# Gripper_Finger.net
KiCad netlist of a schematic drawn in EAGLE
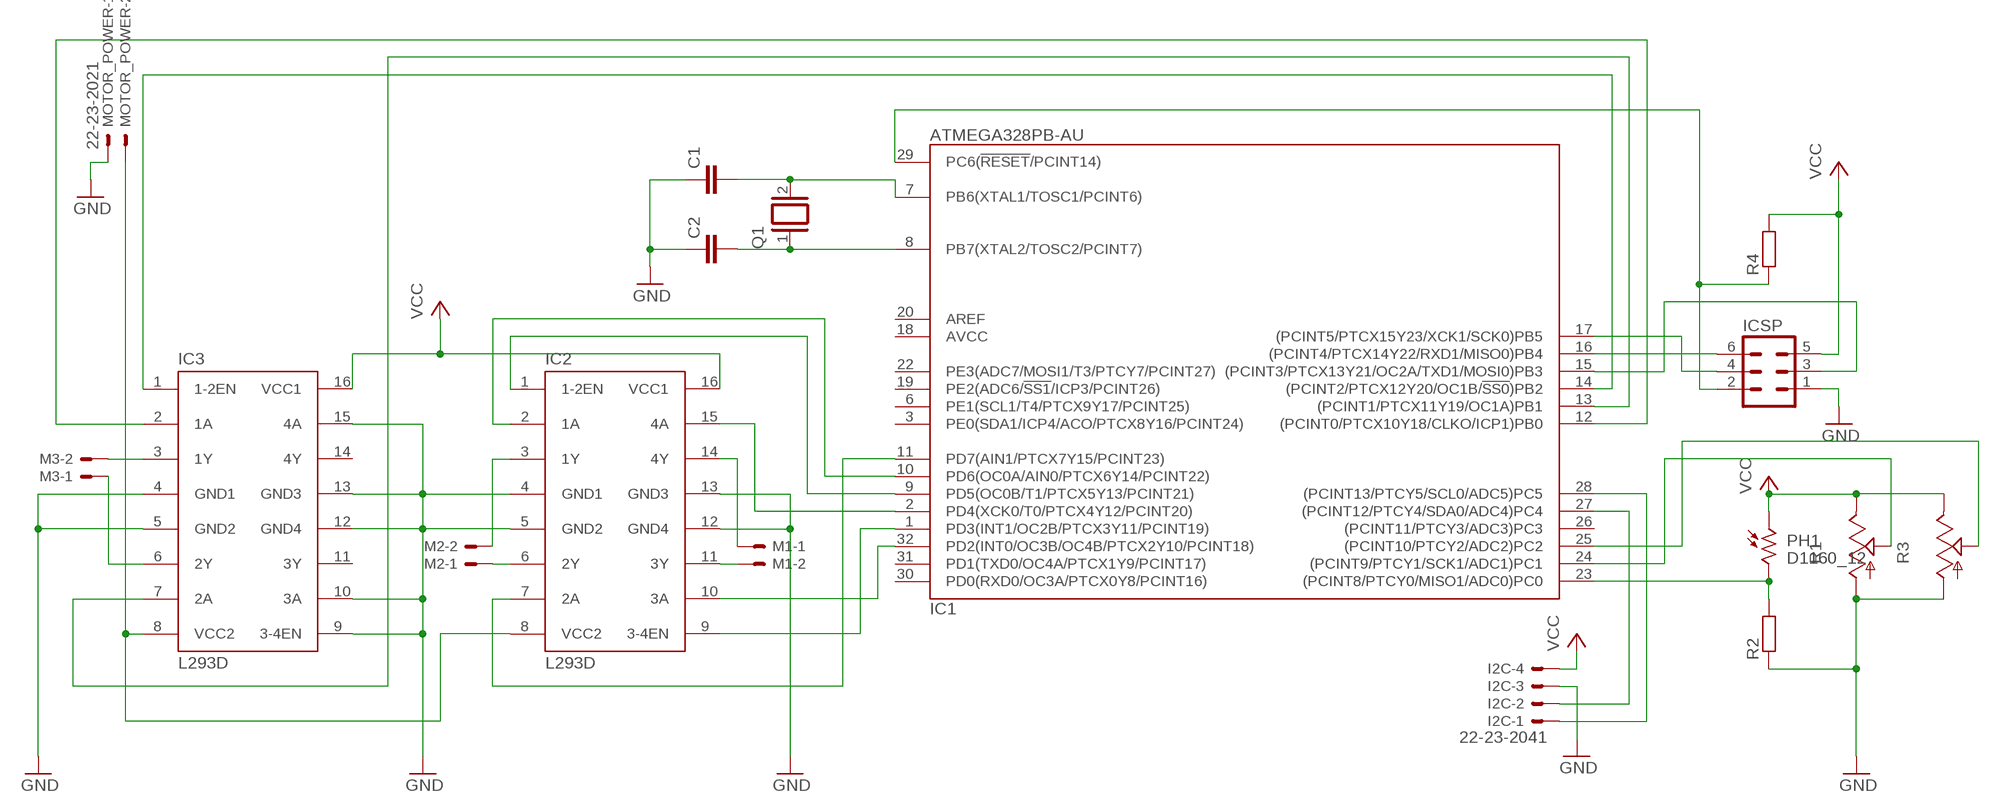
[diagram p0: schematic, sheet 1]

(export (version "E")
  (design (tool "Eeschema 10.0.6"))
  (components
    (comp (ref "C1")
      (value "C2.5/2")
      (footprint "eagle-import:C2.5-2")
      (libsource (lib "eagle-import") (part "C2.5/2"))
    )
    (comp (ref "C2")
      (value "C2.5/2")
      (footprint "eagle-import:C2.5-2")
      (libsource (lib "eagle-import") (part "C2.5/2"))
    )
    (comp (ref "I2C")
      (value "22-23-2041")
      (footprint "eagle-import:22-23-2041")
      (fields (field (name "MF") "MOLEX"))
      (libsource (lib "eagle-import") (part "22-23-2041"))
    )
    (comp (ref "IC1")
      (value "ATMEGA328PB-AU")
      (footprint "eagle-import:QFP32_7X7_0.80")
      (libsource (lib "eagle-import") (part "ATMEGA328PB-AU"))
    )
    (comp (ref "IC2")
      (value "L293D")
      (footprint "eagle-import:DIL16")
      (libsource (lib "eagle-import") (part "L293D"))
    )
    (comp (ref "IC3")
      (value "L293D")
      (footprint "eagle-import:DIL16")
      (libsource (lib "eagle-import") (part "L293D"))
    )
    (comp (ref "ICSP")
      (value "MA03-2")
      (footprint "eagle-import:MA03-2")
      (libsource (lib "eagle-import") (part "MA03-2"))
    )
    (comp (ref "M1")
      (value "22-23-2021")
      (footprint "eagle-import:22-23-2021")
      (fields (field (name "MF") "MOLEX"))
      (libsource (lib "eagle-import") (part "22-23-2021"))
    )
    (comp (ref "M2")
      (value "22-23-2021")
      (footprint "eagle-import:22-23-2021")
      (fields (field (name "MF") "MOLEX"))
      (libsource (lib "eagle-import") (part "22-23-2021"))
    )
    (comp (ref "M3")
      (value "22-23-2021")
      (footprint "eagle-import:22-23-2021")
      (fields (field (name "MF") "MOLEX"))
      (libsource (lib "eagle-import") (part "22-23-2021"))
    )
    (comp (ref "MOTOR_POWER")
      (value "22-23-2021")
      (footprint "eagle-import:22-23-2021")
      (fields (field (name "MF") "MOLEX"))
      (libsource (lib "eagle-import") (part "22-23-2021"))
    )
    (comp (ref "PH1")
      (value "D1160_12")
      (footprint "eagle-import:D11XX")
      (libsource (lib "eagle-import") (part "D1160_12"))
    )
    (comp (ref "Q1")
      (value "XTAL/S")
      (footprint "eagle-import:QS")
      (libsource (lib "eagle-import") (part "XTAL/S"))
    )
    (comp (ref "R1")
      (value "TRIM_US-B64Y")
      (footprint "eagle-import:B64Y")
      (libsource (lib "eagle-import") (part "TRIM_US-B64Y"))
    )
    (comp (ref "R2")
      (value "R-EU_0204/5")
      (footprint "eagle-import:0204_5")
      (libsource (lib "eagle-import") (part "R-EU_0204/5"))
    )
    (comp (ref "R3")
      (value "TRIM_US-B64Y")
      (footprint "eagle-import:B64Y")
      (libsource (lib "eagle-import") (part "TRIM_US-B64Y"))
    )
    (comp (ref "R4")
      (value "R-EU_0204/5")
      (footprint "eagle-import:0204_5")
      (libsource (lib "eagle-import") (part "R-EU_0204/5"))
    )
  )
  (nets
    (net (code "1") (name "/AVCC") (class "Default")
      (node (ref "IC1") (pin "18") (pinfunction "AVCC_18") (pintype "power_in"))
    )
    (net (code "2") (name "GND") (class "Default")
      (node (ref "C1") (pin "1") (pinfunction "1_1") (pintype "passive"))
      (node (ref "C2") (pin "1") (pinfunction "1_1") (pintype "passive"))
      (node (ref "I2C") (pin "3") (pinfunction "S_3") (pintype "passive"))
      (node (ref "IC2") (pin "12") (pinfunction "GND4_12") (pintype "power_in"))
      (node (ref "IC2") (pin "13") (pinfunction "GND3_13") (pintype "power_in"))
      (node (ref "IC2") (pin "4") (pinfunction "GND1_4") (pintype "power_in"))
      (node (ref "IC2") (pin "5") (pinfunction "GND2_5") (pintype "power_in"))
      (node (ref "IC3") (pin "10") (pinfunction "3A_10") (pintype "input"))
      (node (ref "IC3") (pin "12") (pinfunction "GND4_12") (pintype "power_in"))
      (node (ref "IC3") (pin "13") (pinfunction "GND3_13") (pintype "power_in"))
      (node (ref "IC3") (pin "15") (pinfunction "4A_15") (pintype "input"))
      (node (ref "IC3") (pin "4") (pinfunction "GND1_4") (pintype "power_in"))
      (node (ref "IC3") (pin "5") (pinfunction "GND2_5") (pintype "power_in"))
      (node (ref "IC3") (pin "9") (pinfunction "3-4EN_9") (pintype "input"))
      (node (ref "ICSP") (pin "1") (pinfunction "1_1") (pintype "passive"))
      (node (ref "MOTOR_POWER") (pin "1") (pinfunction "S_1") (pintype "passive"))
      (node (ref "R1") (pin "A") (pinfunction "A_A") (pintype "passive"))
      (node (ref "R2") (pin "1") (pinfunction "1_1") (pintype "passive"))
      (node (ref "R3") (pin "A") (pinfunction "A_A") (pintype "passive"))
    )
    (net (code "3") (name "Net-(I2CA-S)") (class "Default")
      (node (ref "I2C") (pin "1") (pinfunction "S_1") (pintype "passive"))
      (node (ref "IC1") (pin "28") (pinfunction "(PCINT13/PTCY5/SCL0/ADC5)PC5_28") (pintype "bidirectional"))
    )
    (net (code "4") (name "Net-(I2CB-S)") (class "Default")
      (node (ref "I2C") (pin "2") (pinfunction "S_2") (pintype "passive"))
      (node (ref "IC1") (pin "27") (pinfunction "(PCINT12/PTCY4/SDA0/ADC4)PC4_27") (pintype "bidirectional"))
    )
    (net (code "5") (name "Net-(IC1A-(PCINT0{slash}PTCX10Y18{slash}CLKO{slash}ICP1)PB0)") (class "Default")
      (node (ref "IC1") (pin "12") (pinfunction "(PCINT0/PTCX10Y18/CLKO/ICP1)PB0_12") (pintype "bidirectional"))
      (node (ref "IC3") (pin "2") (pinfunction "1A_2") (pintype "input"))
    )
    (net (code "6") (name "Net-(IC1A-(PCINT1{slash}PTCX11Y19{slash}OC1A)PB1)") (class "Default")
      (node (ref "IC1") (pin "13") (pinfunction "(PCINT1/PTCX11Y19/OC1A)PB1_13") (pintype "bidirectional"))
      (node (ref "IC3") (pin "7") (pinfunction "2A_7") (pintype "input"))
    )
    (net (code "7") (name "Net-(IC1A-(PCINT2{slash}PTCX12Y20{slash}OC1B{slash}~{SS0})PB2)") (class "Default")
      (node (ref "IC1") (pin "14") (pinfunction "(PCINT2/PTCX12Y20/OC1B/~{SS0})PB2_14") (pintype "bidirectional"))
      (node (ref "IC3") (pin "1") (pinfunction "1-2EN_1") (pintype "input"))
    )
    (net (code "8") (name "Net-(IC1A-(PCINT3{slash}PTCX13Y21{slash}OC2A{slash}TXD1{slash}MOSI0)PB3)") (class "Default")
      (node (ref "IC1") (pin "15") (pinfunction "(PCINT3/PTCX13Y21/OC2A/TXD1/MOSI0)PB3_15") (pintype "bidirectional"))
      (node (ref "ICSP") (pin "3") (pinfunction "3_3") (pintype "passive"))
    )
    (net (code "9") (name "Net-(IC1A-(PCINT4{slash}PTCX14Y22{slash}RXD1{slash}MISO0)PB4)") (class "Default")
      (node (ref "IC1") (pin "16") (pinfunction "(PCINT4/PTCX14Y22/RXD1/MISO0)PB4_16") (pintype "bidirectional"))
      (node (ref "ICSP") (pin "6") (pinfunction "6_6") (pintype "passive"))
    )
    (net (code "10") (name "Net-(IC1A-(PCINT5{slash}PTCX15Y23{slash}XCK1{slash}SCK0)PB5)") (class "Default")
      (node (ref "IC1") (pin "17") (pinfunction "(PCINT5/PTCX15Y23/XCK1/SCK0)PB5_17") (pintype "bidirectional"))
      (node (ref "ICSP") (pin "4") (pinfunction "4_4") (pintype "passive"))
    )
    (net (code "11") (name "Net-(IC1A-(PCINT8{slash}PTCY0{slash}MISO1{slash}ADC0)PC0)") (class "Default")
      (node (ref "IC1") (pin "23") (pinfunction "(PCINT8/PTCY0/MISO1/ADC0)PC0_23") (pintype "bidirectional"))
      (node (ref "PH1") (pin "2") (pinfunction "2_2") (pintype "passive"))
      (node (ref "R2") (pin "2") (pinfunction "2_2") (pintype "passive"))
    )
    (net (code "12") (name "Net-(IC1A-(PCINT9{slash}PTCY1{slash}SCK1{slash}ADC1)PC1)") (class "Default")
      (node (ref "IC1") (pin "24") (pinfunction "(PCINT9/PTCY1/SCK1/ADC1)PC1_24") (pintype "bidirectional"))
      (node (ref "R1") (pin "S") (pinfunction "S_S") (pintype "passive"))
    )
    (net (code "13") (name "Net-(IC1A-(PCINT10{slash}PTCY2{slash}ADC2)PC2)") (class "Default")
      (node (ref "IC1") (pin "25") (pinfunction "(PCINT10/PTCY2/ADC2)PC2_25") (pintype "bidirectional"))
      (node (ref "R3") (pin "S") (pinfunction "S_S") (pintype "passive"))
    )
    (net (code "14") (name "Net-(IC1A-PB6(XTAL1{slash}TOSC1{slash}PCINT6))") (class "Default")
      (node (ref "C1") (pin "2") (pinfunction "2_2") (pintype "passive"))
      (node (ref "IC1") (pin "7") (pinfunction "PB6(XTAL1/TOSC1/PCINT6)_7") (pintype "bidirectional"))
      (node (ref "Q1") (pin "2") (pinfunction "2_2") (pintype "passive"))
    )
    (net (code "15") (name "Net-(IC1A-PB7(XTAL2{slash}TOSC2{slash}PCINT7))") (class "Default")
      (node (ref "C2") (pin "2") (pinfunction "2_2") (pintype "passive"))
      (node (ref "IC1") (pin "8") (pinfunction "PB7(XTAL2/TOSC2/PCINT7)_8") (pintype "bidirectional"))
      (node (ref "Q1") (pin "1") (pinfunction "1_1") (pintype "passive"))
    )
    (net (code "16") (name "Net-(IC1A-PC6(~{RESET}{slash}PCINT14))") (class "Default")
      (node (ref "IC1") (pin "29") (pinfunction "PC6(~{RESET}/PCINT14)_29") (pintype "bidirectional"))
      (node (ref "ICSP") (pin "2") (pinfunction "2_2") (pintype "passive"))
      (node (ref "R4") (pin "1") (pinfunction "1_1") (pintype "passive"))
    )
    (net (code "17") (name "Net-(IC1A-PD2(INT0{slash}OC3B{slash}OC4B{slash}PTCX2Y10{slash}PCINT18))") (class "Default")
      (node (ref "IC1") (pin "32") (pinfunction "PD2(INT0/OC3B/OC4B/PTCX2Y10/PCINT18)_32") (pintype "bidirectional"))
      (node (ref "IC2") (pin "10") (pinfunction "3A_10") (pintype "input"))
    )
    (net (code "18") (name "Net-(IC1A-PD3(INT1{slash}OC2B{slash}PTCX3Y11{slash}PCINT19))") (class "Default")
      (node (ref "IC1") (pin "1") (pinfunction "PD3(INT1/OC2B/PTCX3Y11/PCINT19)_1") (pintype "bidirectional"))
      (node (ref "IC2") (pin "9") (pinfunction "3-4EN_9") (pintype "input"))
    )
    (net (code "19") (name "Net-(IC1A-PD4(XCK0{slash}T0{slash}PTCX4Y12{slash}PCINT20))") (class "Default")
      (node (ref "IC1") (pin "2") (pinfunction "PD4(XCK0/T0/PTCX4Y12/PCINT20)_2") (pintype "bidirectional"))
      (node (ref "IC2") (pin "15") (pinfunction "4A_15") (pintype "input"))
    )
    (net (code "20") (name "Net-(IC1A-PD5(OC0B{slash}T1{slash}PTCX5Y13{slash}PCINT21))") (class "Default")
      (node (ref "IC1") (pin "9") (pinfunction "PD5(OC0B/T1/PTCX5Y13/PCINT21)_9") (pintype "bidirectional"))
      (node (ref "IC2") (pin "1") (pinfunction "1-2EN_1") (pintype "input"))
    )
    (net (code "21") (name "Net-(IC1A-PD6(OC0A{slash}AIN0{slash}PTCX6Y14{slash}PCINT22))") (class "Default")
      (node (ref "IC1") (pin "10") (pinfunction "PD6(OC0A/AIN0/PTCX6Y14/PCINT22)_10") (pintype "bidirectional"))
      (node (ref "IC2") (pin "2") (pinfunction "1A_2") (pintype "input"))
    )
    (net (code "22") (name "Net-(IC1A-PD7(AIN1{slash}PTCX7Y15{slash}PCINT23))") (class "Default")
      (node (ref "IC1") (pin "11") (pinfunction "PD7(AIN1/PTCX7Y15/PCINT23)_11") (pintype "bidirectional"))
      (node (ref "IC2") (pin "7") (pinfunction "2A_7") (pintype "input"))
    )
    (net (code "23") (name "Net-(IC2-1Y)") (class "Default")
      (node (ref "IC2") (pin "3") (pinfunction "1Y_3") (pintype "output"))
      (node (ref "M2") (pin "2") (pinfunction "S_2") (pintype "passive"))
    )
    (net (code "24") (name "Net-(IC2-2Y)") (class "Default")
      (node (ref "IC2") (pin "6") (pinfunction "2Y_6") (pintype "output"))
      (node (ref "M2") (pin "1") (pinfunction "S_1") (pintype "passive"))
    )
    (net (code "25") (name "Net-(IC2-3Y)") (class "Default")
      (node (ref "IC2") (pin "11") (pinfunction "3Y_11") (pintype "output"))
      (node (ref "M1") (pin "2") (pinfunction "S_2") (pintype "passive"))
    )
    (net (code "26") (name "Net-(IC2-4Y)") (class "Default")
      (node (ref "IC2") (pin "14") (pinfunction "4Y_14") (pintype "output"))
      (node (ref "M1") (pin "1") (pinfunction "S_1") (pintype "passive"))
    )
    (net (code "27") (name "Net-(IC2-VCC2)") (class "Default")
      (node (ref "IC2") (pin "8") (pinfunction "VCC2_8") (pintype "power_in"))
      (node (ref "IC3") (pin "8") (pinfunction "VCC2_8") (pintype "power_in"))
      (node (ref "MOTOR_POWER") (pin "2") (pinfunction "S_2") (pintype "passive"))
    )
    (net (code "28") (name "Net-(IC3-1Y)") (class "Default")
      (node (ref "IC3") (pin "3") (pinfunction "1Y_3") (pintype "output"))
      (node (ref "M3") (pin "2") (pinfunction "S_2") (pintype "passive"))
    )
    (net (code "29") (name "Net-(IC3-2Y)") (class "Default")
      (node (ref "IC3") (pin "6") (pinfunction "2Y_6") (pintype "output"))
      (node (ref "M3") (pin "1") (pinfunction "S_1") (pintype "passive"))
    )
    (net (code "30") (name "VCC") (class "Default")
      (node (ref "I2C") (pin "4") (pinfunction "S_4") (pintype "passive"))
      (node (ref "IC2") (pin "16") (pinfunction "VCC1_16") (pintype "power_in"))
      (node (ref "IC3") (pin "16") (pinfunction "VCC1_16") (pintype "power_in"))
      (node (ref "ICSP") (pin "5") (pinfunction "5_5") (pintype "passive"))
      (node (ref "PH1") (pin "1") (pinfunction "1_1") (pintype "passive"))
      (node (ref "R1") (pin "E") (pinfunction "E_E") (pintype "passive"))
      (node (ref "R3") (pin "E") (pinfunction "E_E") (pintype "passive"))
      (node (ref "R4") (pin "2") (pinfunction "2_2") (pintype "passive"))
    )
    (net (code "31") (name "unconnected-(IC1A-(PCINT11{slash}PTCY3{slash}ADC3)PC3-Pad26)") (class "Default")
      (node (ref "IC1") (pin "26") (pinfunction "(PCINT11/PTCY3/ADC3)PC3_26") (pintype "bidirectional"))
    )
    (net (code "32") (name "unconnected-(IC1A-AREF-Pad20)") (class "Default")
      (node (ref "IC1") (pin "20") (pinfunction "AREF_20") (pintype "passive"))
    )
    (net (code "33") (name "unconnected-(IC1A-PD0(RXD0{slash}OC3A{slash}PTCX0Y8{slash}PCINT16)-Pad30)") (class "Default")
      (node (ref "IC1") (pin "30") (pinfunction "PD0(RXD0/OC3A/PTCX0Y8/PCINT16)_30") (pintype "bidirectional"))
    )
    (net (code "34") (name "unconnected-(IC1A-PD1(TXD0{slash}OC4A{slash}PTCX1Y9{slash}PCINT17)-Pad31)") (class "Default")
      (node (ref "IC1") (pin "31") (pinfunction "PD1(TXD0/OC4A/PTCX1Y9/PCINT17)_31") (pintype "bidirectional"))
    )
    (net (code "35") (name "unconnected-(IC1A-PE0(SDA1{slash}ICP4{slash}ACO{slash}PTCX8Y16{slash}PCINT24)-Pad3)") (class "Default")
      (node (ref "IC1") (pin "3") (pinfunction "PE0(SDA1/ICP4/ACO/PTCX8Y16/PCINT24)_3") (pintype "bidirectional"))
    )
    (net (code "36") (name "unconnected-(IC1A-PE1(SCL1{slash}T4{slash}PTCX9Y17{slash}PCINT25)-Pad6)") (class "Default")
      (node (ref "IC1") (pin "6") (pinfunction "PE1(SCL1/T4/PTCX9Y17/PCINT25)_6") (pintype "bidirectional"))
    )
    (net (code "37") (name "unconnected-(IC1A-PE2(ADC6{slash}~{SS1}{slash}ICP3{slash}PCINT26)-Pad19)") (class "Default")
      (node (ref "IC1") (pin "19") (pinfunction "PE2(ADC6/~{SS1}/ICP3/PCINT26)_19") (pintype "bidirectional"))
    )
    (net (code "38") (name "unconnected-(IC1A-PE3(ADC7{slash}MOSI1{slash}T3{slash}PTCY7{slash}PCINT27)-Pad22)") (class "Default")
      (node (ref "IC1") (pin "22") (pinfunction "PE3(ADC7/MOSI1/T3/PTCY7/PCINT27)_22") (pintype "bidirectional"))
    )
    (net (code "39") (name "unconnected-(IC3-3Y-Pad11)") (class "Default")
      (node (ref "IC3") (pin "11") (pinfunction "3Y_11") (pintype "output"))
    )
    (net (code "40") (name "unconnected-(IC3-4Y-Pad14)") (class "Default")
      (node (ref "IC3") (pin "14") (pinfunction "4Y_14") (pintype "output"))
    )
  )
)
